# MAX31855_Breakout_v10.net
KiCad netlist of a schematic drawn in EAGLE
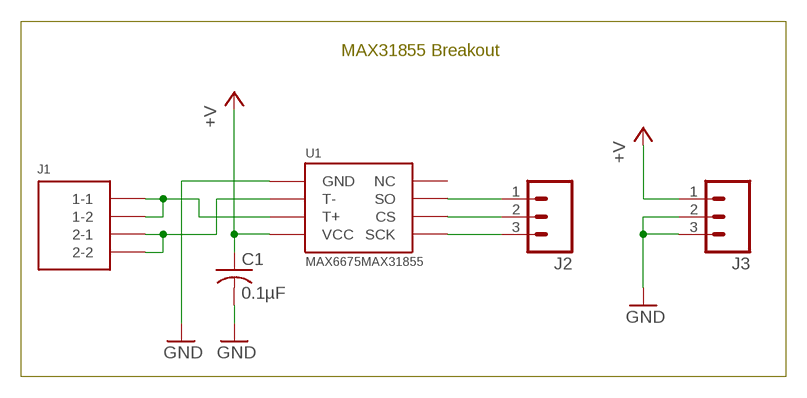
[diagram p0: schematic, sheet 1]

(export (version "E")
  (design (tool "Eeschema 10.0.6"))
  (components
    (comp (ref "C1")
      (value "0.1µF")
      (footprint "eagle-import:C0603")
      (libsource (lib "eagle-import") (part "C-USC0603"))
    )
    (comp (ref "J1")
      (value "WIRE-TO-BOARD_2PIN_SMD")
      (footprint "eagle-import:WIRE-TO-BOARD_SMD_2WAY")
      (libsource (lib "eagle-import") (part "WIRE-TO-BOARD_2PIN_SMD"))
    )
    (comp (ref "J2")
      (value "M031X03_NO_SILK")
      (footprint "eagle-import:1X03_NO_SILK")
      (libsource (lib "eagle-import") (part "M031X03_NO_SILK"))
    )
    (comp (ref "J3")
      (value "M031X03_NO_SILK")
      (footprint "eagle-import:1X03_NO_SILK")
      (libsource (lib "eagle-import") (part "M031X03_NO_SILK"))
    )
    (comp (ref "U1")
      (value "MAX6675MAX31855")
      (footprint "eagle-import:SOIC-8")
      (libsource (lib "eagle-import") (part "MAX6675MAX31855"))
    )
  )
  (nets
    (net (code "1") (name "+V") (class "Default")
      (node (ref "C1") (pin "1") (pinfunction "1_1") (pintype "passive"))
      (node (ref "J3") (pin "1") (pinfunction "1_1") (pintype "passive"))
      (node (ref "U1") (pin "VCC") (pinfunction "VCC_VCC") (pintype "bidirectional"))
    )
    (net (code "2") (name "GND") (class "Default")
      (node (ref "C1") (pin "2") (pinfunction "2_2") (pintype "passive"))
      (node (ref "J3") (pin "2") (pinfunction "2_2") (pintype "passive"))
      (node (ref "J3") (pin "3") (pinfunction "3_3") (pintype "passive"))
      (node (ref "U1") (pin "GND") (pinfunction "GND_GND") (pintype "bidirectional"))
    )
    (net (code "3") (name "Net-(J1-1-1)") (class "Default")
      (node (ref "J1") (pin "P1-1") (pinfunction "1-1_P1-1") (pintype "bidirectional"))
      (node (ref "J1") (pin "P1-2") (pinfunction "1-2_P1-2") (pintype "bidirectional"))
      (node (ref "U1") (pin "T+") (pinfunction "T+_T+") (pintype "bidirectional"))
    )
    (net (code "4") (name "Net-(J1-2-1)") (class "Default")
      (node (ref "J1") (pin "P2-1") (pinfunction "2-1_P2-1") (pintype "bidirectional"))
      (node (ref "J1") (pin "P2-2") (pinfunction "2-2_P2-2") (pintype "bidirectional"))
      (node (ref "U1") (pin "T-") (pinfunction "T-_T-") (pintype "bidirectional"))
    )
    (net (code "5") (name "Net-(J2-Pad1)") (class "Default")
      (node (ref "J2") (pin "1") (pinfunction "1_1") (pintype "passive"))
      (node (ref "U1") (pin "SO") (pinfunction "SO_SO") (pintype "bidirectional"))
    )
    (net (code "6") (name "Net-(J2-Pad2)") (class "Default")
      (node (ref "J2") (pin "2") (pinfunction "2_2") (pintype "passive"))
      (node (ref "U1") (pin "CS") (pinfunction "CS_CS") (pintype "bidirectional"))
    )
    (net (code "7") (name "Net-(J2-Pad3)") (class "Default")
      (node (ref "J2") (pin "3") (pinfunction "3_3") (pintype "passive"))
      (node (ref "U1") (pin "SCK") (pinfunction "SCK_SCK") (pintype "bidirectional"))
    )
    (net (code "8") (name "unconnected-(U1-PadNC)") (class "Default")
      (node (ref "U1") (pin "NC") (pinfunction "NC_NC") (pintype "no_connect"))
    )
  )
)
